# Sheet1.net
KiCad netlist of a schematic drawn in Altium Designer
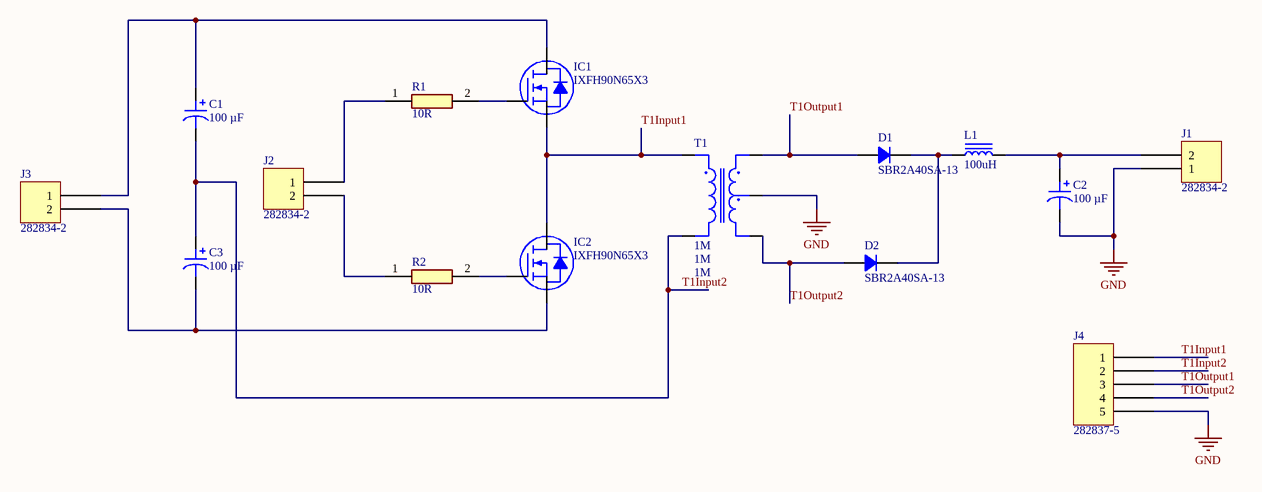
[diagram p0: Sheet1.SchDoc]

(export (version "E")
  (design (tool "Eeschema 10.0.6"))
  (components
    (comp (ref "C1")
      (value "100 µF")
      (footprint "CAP AL TH D8 L3.5 H12.5")
      (description "CAP ALUM 100UF 20% 25V RADIAL")
      (fields (field (name "PART NUMBER") "UKL1E101MPD1TD") (field (name "MANUFACTURER") "Nichicon"))
      (libsource (lib "Celestial Altium Library - altium_library") (part "Polarised Capacitor"))
    )
    (comp (ref "C2")
      (value "100 µF")
      (footprint "CAP AL TH D8 L3.5 H12.5")
      (description "CAP ALUM 100UF 20% 25V RADIAL")
      (fields (field (name "PART NUMBER") "UKL1E101MPD1TD") (field (name "MANUFACTURER") "Nichicon"))
      (libsource (lib "Celestial Altium Library - altium_library") (part "Polarised Capacitor"))
    )
    (comp (ref "C3")
      (value "100 µF")
      (footprint "CAP AL TH D8 L3.5 H12.5")
      (description "CAP ALUM 100UF 20% 25V RADIAL")
      (fields (field (name "PART NUMBER") "UKL1E101MPD1TD") (field (name "MANUFACTURER") "Nichicon"))
      (libsource (lib "Celestial Altium Library - altium_library") (part "Polarised Capacitor"))
    )
    (comp (ref "D1")
      (value "SBR2A40SA-13")
      (footprint "DO214AC SMA")
      (description "DIODE SBR 40V 2A SMA")
      (fields (field (name "MANUFACTURER") "Diodes Incorporated"))
      (libsource (lib "Celestial Altium Library - altium_library") (part "Diode"))
    )
    (comp (ref "D2")
      (value "SBR2A40SA-13")
      (footprint "DO214AC SMA")
      (description "DIODE SBR 40V 2A SMA")
      (fields (field (name "MANUFACTURER") "Diodes Incorporated"))
      (libsource (lib "Celestial Altium Library - altium_library") (part "Diode"))
    )
    (comp (ref "IC1")
      (value "IXFH90N65X3")
      (footprint "IXYS TO-247 IXFH FLAT")
      (description "MOSFET 90A 650V X3 TO247")
      (fields (field (name "MANUFACTURER") "IXYS"))
      (libsource (lib "Celestial Altium Library - altium_library") (part "MOSFET SINGLE GDS"))
    )
    (comp (ref "IC2")
      (value "IXFH90N65X3")
      (footprint "IXYS TO-247 IXFH FLAT")
      (description "MOSFET 90A 650V X3 TO247")
      (fields (field (name "MANUFACTURER") "IXYS"))
      (libsource (lib "Celestial Altium Library - altium_library") (part "MOSFET SINGLE GDS"))
    )
    (comp (ref "J1")
      (value "282834-2")
      (footprint "TE 282834-2")
      (description "TERM BLK 2P SIDE ENT 2.54MM PCB")
      (fields (field (name "MANUFACTURER") "TE Connectivity AMP Connectors") (field (name "VOLTAGE") "150V"))
      (libsource (lib "") (part "2 Pin_1"))
    )
    (comp (ref "J2")
      (value "282834-2")
      (footprint "TE 282834-2")
      (description "TERM BLK 2P SIDE ENT 2.54MM PCB")
      (fields (field (name "MANUFACTURER") "TE Connectivity AMP Connectors") (field (name "VOLTAGE") "150V"))
      (libsource (lib "Celestial Altium Library - altium_library") (part "2 Pin"))
    )
    (comp (ref "J3")
      (value "282834-2")
      (footprint "TE 282834-2")
      (description "TERM BLK 2P SIDE ENT 2.54MM PCB")
      (fields (field (name "MANUFACTURER") "TE Connectivity AMP Connectors") (field (name "VOLTAGE") "150V"))
      (libsource (lib "Celestial Altium Library - altium_library") (part "2 Pin"))
    )
    (comp (ref "J4")
      (value "282837-5")
      (footprint "TE 282837-5")
      (description "TERM BLK 5P SIDE ENT 5.08MM PCB")
      (fields (field (name "MANUFACTURER") "TE Connectivity AMP Connectors") (field (name "VOLTAGE") "300V"))
      (libsource (lib "Celestial Altium Library - altium_library") (part "5 Pin"))
    )
    (comp (ref "L1")
      (value "100uH")
      (footprint "BOURNS SRR1280")
      (description "FIXED IND 270UH 1.2A 450MOHM SMD")
      (fields (field (name "PART NUMBER") "SRR1280-271K") (field (name "MANUFACTURER") "Bourns Inc."))
      (libsource (lib "Celestial Altium Library - altium_library") (part "Inductor"))
    )
    (comp (ref "R1")
      (value "10R")
      (footprint "SamacSys:RESAD1680W59L680D250")
      (description "Resistor")
      (fields (field (name "MANUFACTURER_PART_NUMBER") "CFR0W4J0300A50"))
      (libsource (lib "*") (part "CFR0W4J0300A50"))
    )
    (comp (ref "R2")
      (value "10R")
      (footprint "SamacSys:RESAD1680W59L680D250")
      (description "Resistor")
      (fields (field (name "MANUFACTURER_PART_NUMBER") "CFR0W4J0300A50"))
      (libsource (lib "*") (part "CFR0W4J0300A50"))
    )
    (comp (ref "T1")
      (value "Ideal Transformer With Central Tap")
      (fields (field (name "L1") "1M") (field (name "L2") "1M") (field (name "L3") "1M"))
      (libsource (lib "Simulation Generic Components") (part "Transformer With Central Tap Ideal"))
    )
  )
  (nets
    (net (code "1") (name "/T1Input1") (class "Default")
      (node (ref "IC1") (pin "S") (pinfunction "S_S") (pintype "passive"))
      (node (ref "IC2") (pin "D") (pinfunction "D_D") (pintype "passive"))
      (node (ref "J4") (pin "1") (pinfunction "1_1") (pintype "passive"))
      (node (ref "T1") (pin "1") (pinfunction "1_1") (pintype "passive"))
    )
    (net (code "2") (name "/T1Input2") (class "Default")
      (node (ref "C1") (pin "2") (pinfunction "2_2") (pintype "passive"))
      (node (ref "C3") (pin "1") (pinfunction "1_1") (pintype "passive"))
      (node (ref "J4") (pin "2") (pinfunction "2_2") (pintype "passive"))
      (node (ref "T1") (pin "2") (pinfunction "2_2") (pintype "passive"))
    )
    (net (code "3") (name "/T1Output1") (class "Default")
      (node (ref "D1") (pin "1") (pinfunction "1_1") (pintype "passive"))
      (node (ref "J4") (pin "3") (pinfunction "3_3") (pintype "passive"))
      (node (ref "T1") (pin "3") (pinfunction "3_3") (pintype "passive"))
    )
    (net (code "4") (name "/T1Output2") (class "Default")
      (node (ref "D2") (pin "1") (pinfunction "1_1") (pintype "passive"))
      (node (ref "J4") (pin "4") (pinfunction "4_4") (pintype "passive"))
      (node (ref "T1") (pin "5") (pinfunction "5_5") (pintype "passive"))
    )
    (net (code "5") (name "GND") (class "Default")
      (node (ref "C2") (pin "2") (pinfunction "2_2") (pintype "passive"))
      (node (ref "J1") (pin "1") (pinfunction "1_1") (pintype "passive"))
      (node (ref "J4") (pin "5") (pinfunction "5_5") (pintype "passive"))
      (node (ref "T1") (pin "4") (pinfunction "4_4") (pintype "passive"))
    )
    (net (code "6") (name "Net-(C1-Pad1)") (class "Default")
      (node (ref "C1") (pin "1") (pinfunction "1_1") (pintype "passive"))
      (node (ref "IC1") (pin "D") (pinfunction "D_D") (pintype "passive"))
      (node (ref "J3") (pin "1") (pinfunction "1_1") (pintype "passive"))
    )
    (net (code "7") (name "Net-(C2-Pad1)") (class "Default")
      (node (ref "C2") (pin "1") (pinfunction "1_1") (pintype "passive"))
      (node (ref "J1") (pin "2") (pinfunction "2_2") (pintype "passive"))
      (node (ref "L1") (pin "2") (pinfunction "2_2") (pintype "passive"))
    )
    (net (code "8") (name "Net-(C3-Pad2)") (class "Default")
      (node (ref "C3") (pin "2") (pinfunction "2_2") (pintype "passive"))
      (node (ref "IC2") (pin "S") (pinfunction "S_S") (pintype "passive"))
      (node (ref "J3") (pin "2") (pinfunction "2_2") (pintype "passive"))
    )
    (net (code "9") (name "Net-(D1-Pad2)") (class "Default")
      (node (ref "D1") (pin "2") (pinfunction "2_2") (pintype "passive"))
      (node (ref "D2") (pin "2") (pinfunction "2_2") (pintype "passive"))
      (node (ref "L1") (pin "1") (pinfunction "1_1") (pintype "passive"))
    )
    (net (code "10") (name "Net-(IC1-PadG)") (class "Default")
      (node (ref "IC1") (pin "G") (pinfunction "G_G") (pintype "passive"))
      (node (ref "R1") (pin "2") (pinfunction "2_2") (pintype "passive"))
    )
    (net (code "11") (name "Net-(IC2-PadG)") (class "Default")
      (node (ref "IC2") (pin "G") (pinfunction "G_G") (pintype "passive"))
      (node (ref "R2") (pin "2") (pinfunction "2_2") (pintype "passive"))
    )
    (net (code "12") (name "Net-(J2-Pad1)") (class "Default")
      (node (ref "J2") (pin "1") (pinfunction "1_1") (pintype "passive"))
      (node (ref "R1") (pin "1") (pinfunction "1_1") (pintype "passive"))
    )
    (net (code "13") (name "Net-(J2-Pad2)") (class "Default")
      (node (ref "J2") (pin "2") (pinfunction "2_2") (pintype "passive"))
      (node (ref "R2") (pin "1") (pinfunction "1_1") (pintype "passive"))
    )
  )
)
